# SunS_fixture_EGSE_External_Supply.net
KiCad netlist of a schematic drawn in Altium Designer
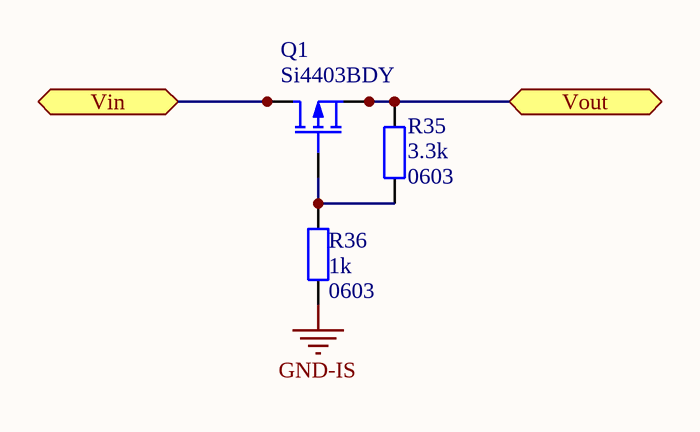
[diagram p0: SunS_fixture_EGSE_External_Supply.SchDoc]

(export (version "E")
  (design (tool "Eeschema 10.0.6"))
  (components
    (comp (ref "Q1")
      (value "Si4403BDY")
      (footprint "SOIC-8_M")
      (description "P-Channel 1.8 V (G-S) MOSFET")
      (libsource (lib "GG") (part "Si4403BDY"))
    )
    (comp (ref "R35")
      (value "3.3k")
      (footprint "SMD_Resistor_0603")
      (description "1k/1% Vishay CRCW 0603 Resistor. 100mW, 100ppm, 75V.")
      (fields
        (field (name "MANUFACTURER") "Vishay")
        (field (name "MANUFACTURERPARTNUMBER") "CRCW06031K00FKxxxx")
        (field (name "PACKAGE") "0603")
      )
      (libsource (lib "resistors") (part "CRCW06031K00FKxxxx"))
    )
    (comp (ref "R36")
      (value "1k")
      (footprint "SMD_Resistor_0603")
      (description "1k/1% Vishay CRCW 0603 Resistor. 100mW, 100ppm, 75V.")
      (fields
        (field (name "MANUFACTURER") "Vishay")
        (field (name "MANUFACTURERPARTNUMBER") "CRCW06031K00FKxxxx")
        (field (name "PACKAGE") "0603")
      )
      (libsource (lib "resistors") (part "CRCW06031K00FKxxxx"))
    )
  )
  (nets
    (net (code "1") (name "/Vin") (class "Default")
      (node (ref "Q1") (pin "5") (pinfunction "D_5") (pintype "passive"))
      (node (ref "Q1") (pin "6") (pinfunction "D_6") (pintype "passive"))
      (node (ref "Q1") (pin "7") (pinfunction "D_7") (pintype "passive"))
      (node (ref "Q1") (pin "8") (pinfunction "D_8") (pintype "passive"))
    )
    (net (code "2") (name "/Vout") (class "Default")
      (node (ref "Q1") (pin "1") (pinfunction "S_1") (pintype "passive"))
      (node (ref "Q1") (pin "2") (pinfunction "S_2") (pintype "passive"))
      (node (ref "Q1") (pin "3") (pinfunction "S_3") (pintype "passive"))
      (node (ref "R35") (pin "1") (pinfunction "1_1") (pintype "passive"))
    )
    (net (code "3") (name "GND-IS") (class "Default")
      (node (ref "R36") (pin "2") (pinfunction "2_2") (pintype "passive"))
    )
    (net (code "4") (name "Net-(Q1-G)") (class "Default")
      (node (ref "Q1") (pin "4") (pinfunction "G_4") (pintype "passive"))
      (node (ref "R35") (pin "2") (pinfunction "2_2") (pintype "passive"))
      (node (ref "R36") (pin "1") (pinfunction "1_1") (pintype "passive"))
    )
  )
)
